# 2_MCU.net
KiCad netlist of a schematic drawn in Altium Designer
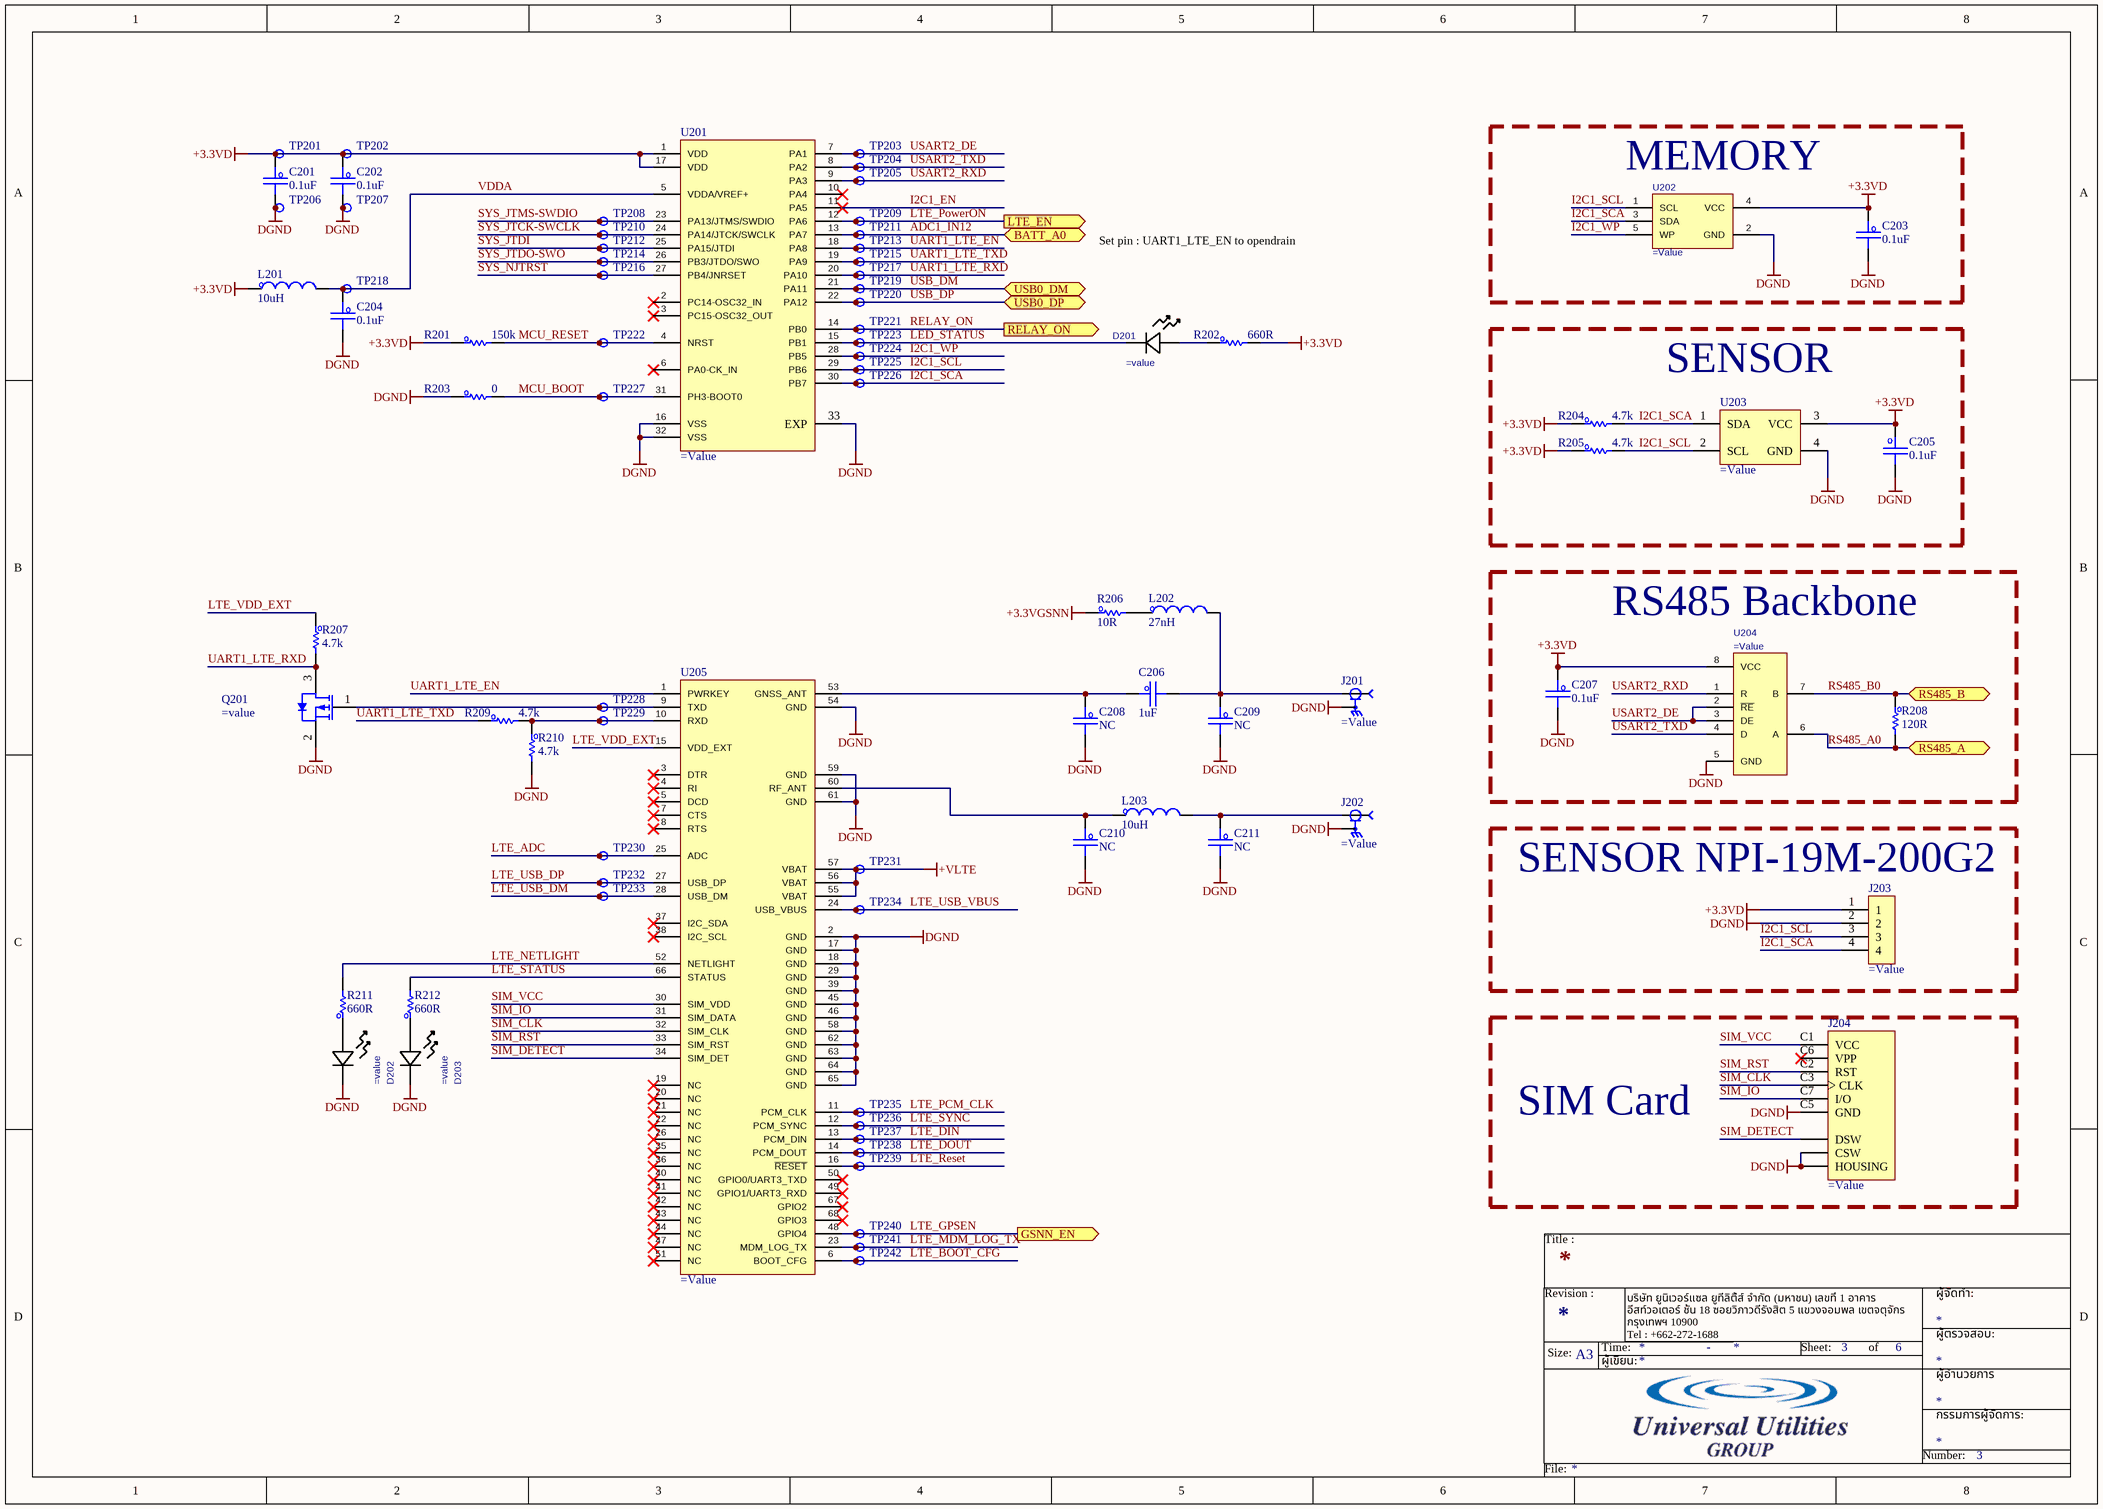
[diagram p0: 2_MCU.SchDoc]

(export (version "E")
  (design (tool "Eeschema 10.0.6"))
  (components
    (comp (ref "C201")
      (value "0.1uF")
      (footprint "C_0603")
      (description "CAP CER 0.1UF 50V X7R 0603")
      (fields (field (name "MANUFACTURER") "KEMET") (field (name "PARTNUMBER") "C0603C104K5RACTU"))
      (libsource (lib "UUSymbol") (part "C_Capacitor"))
    )
    (comp (ref "C202")
      (value "0.1uF")
      (footprint "C_0603")
      (description "CAP CER 0.1UF 50V X7R 0603")
      (fields (field (name "MANUFACTURER") "KEMET") (field (name "PARTNUMBER") "C0603C104K5RACTU"))
      (libsource (lib "UUSymbol") (part "C_Capacitor"))
    )
    (comp (ref "C203")
      (value "0.1uF")
      (footprint "C_0603")
      (description "CAP CER 0.1UF 50V X7R 0603")
      (fields (field (name "MANUFACTURER") "KEMET") (field (name "PARTNUMBER") "C0603C104K5RACTU"))
      (libsource (lib "UUSymbol") (part "C_Capacitor"))
    )
    (comp (ref "C204")
      (value "0.1uF")
      (footprint "C_0603")
      (description "CAP CER 0.1UF 50V X7R 0603")
      (fields (field (name "MANUFACTURER") "KEMET") (field (name "PARTNUMBER") "C0603C104K5RACTU"))
      (libsource (lib "UUSymbol") (part "C_Capacitor"))
    )
    (comp (ref "C205")
      (value "0.1uF")
      (footprint "C_0603")
      (description "CAP CER 0.1UF 50V X7R 0603")
      (fields (field (name "MANUFACTURER") "KEMET") (field (name "PARTNUMBER") "C0603C104K5RACTU"))
      (libsource (lib "UUSymbol") (part "C_Capacitor"))
    )
    (comp (ref "C206")
      (value "1uF")
      (footprint "C_0603")
      (description "Capacitor")
      (libsource (lib "UUSymbol") (part "C_Capacitor"))
    )
    (comp (ref "C207")
      (value "0.1uF")
      (footprint "C_0603")
      (description "CAP CER 0.1UF 50V X7R 0603")
      (fields (field (name "MANUFACTURER") "KEMET") (field (name "PARTNUMBER") "C0603C104K5RACTU"))
      (libsource (lib "UUSymbol") (part "C_Capacitor"))
    )
    (comp (ref "C208")
      (value "NC")
      (footprint "C_0603")
      (description "Capacitor")
      (libsource (lib "UUSymbol") (part "C_Capacitor"))
    )
    (comp (ref "C209")
      (value "NC")
      (footprint "C_0603")
      (description "Capacitor")
      (libsource (lib "UUSymbol") (part "C_Capacitor"))
    )
    (comp (ref "C210")
      (value "NC")
      (footprint "C_0603")
      (description "Capacitor")
      (libsource (lib "UUSymbol") (part "C_Capacitor"))
    )
    (comp (ref "C211")
      (value "NC")
      (footprint "C_0603")
      (description "Capacitor")
      (libsource (lib "UUSymbol") (part "C_Capacitor"))
    )
    (comp (ref "D201")
      (value "~")
      (footprint "LED_0VS75000_WRE")
      (description "LED BLUE CLEAR 0603 SMD")
      (fields (field (name "MANUFACTURER") "Wurth Electronics") (field (name "PARTNUMBER") "150060VS75000"))
      (libsource (lib "UUSymbol") (part "D_LED_150060BS75000"))
    )
    (comp (ref "D202")
      (value "~")
      (footprint "LED_0VS75000_WRE")
      (description "LED BLUE CLEAR 0603 SMD")
      (fields (field (name "MANUFACTURER") "Wurth Electronics") (field (name "PARTNUMBER") "150060VS75000"))
      (libsource (lib "UUSymbol") (part "D_LED_150060BS75000"))
    )
    (comp (ref "D203")
      (value "~")
      (footprint "LED_0VS75000_WRE")
      (description "LED BLUE CLEAR 0603 SMD")
      (fields (field (name "MANUFACTURER") "Wurth Electronics") (field (name "PARTNUMBER") "150060VS75000"))
      (libsource (lib "UUSymbol") (part "D_LED_150060BS75000"))
    )
    (comp (ref "J201")
      (value "~")
      (footprint "MOLEX_0734120114")
      (description "CONN UMC RCPT STR 50 OHM SMD")
      (fields (field (name "PARTNUMBER") "0734120114") (field (name "MANUFACTURER") "Molex"))
      (libsource (lib "UUSymbol") (part "CON_U.FL"))
    )
    (comp (ref "J202")
      (value "~")
      (footprint "MOLEX_0734120114")
      (description "CONN UMC RCPT STR 50 OHM SMD")
      (fields (field (name "PARTNUMBER") "0734120114") (field (name "MANUFACTURER") "Molex"))
      (libsource (lib "UUSymbol") (part "CON_U.FL"))
    )
    (comp (ref "J203")
      (value "~")
      (footprint "CON_4P_PADSENSOR")
      (description "Connector 4 position")
      (libsource (lib "UUSymbol") (part "CON_4P_Heder"))
    )
    (comp (ref "J204")
      (value "~")
      (footprint "JAE_SF72S006VBDR2500")
      (description "NANO SIM CARD CONNECTOR")
      (fields (field (name "PARTNUMBER") "SF72S006VBDR2500") (field (name "MANUFACTURER") "JAE Electronics"))
      (libsource (lib "UUSymbol") (part "CON_SIM_NanoSP"))
    )
    (comp (ref "L201")
      (value "10uH")
      (footprint "L_0603")
      (description "10µH Shielded Multilayer Inductor 250mA 1.05Ohm 0603 (1608 Metric)")
      (fields (field (name "MANUFACTURER") "TDK Corporation") (field (name "PARTNUMBER") "MLZ1608M100WT000"))
      (libsource (lib "UUSymbol") (part "L_Inductor"))
    )
    (comp (ref "L202")
      (value "27nH")
      (footprint "L_0603")
      (description "10µH Shielded Multilayer Inductor 250mA 1.05Ohm 0603 (1608 Metric)")
      (fields (field (name "MANUFACTURER") "TDK Corporation") (field (name "PARTNUMBER") "MLZ1608M100WT000"))
      (libsource (lib "UUSymbol") (part "L_Inductor"))
    )
    (comp (ref "L203")
      (value "10uH")
      (footprint "L_0603")
      (description "10µH Shielded Multilayer Inductor 250mA 1.05Ohm 0603 (1608 Metric)")
      (fields (field (name "MANUFACTURER") "TDK Corporation") (field (name "PARTNUMBER") "MLZ1608M100WT000"))
      (libsource (lib "UUSymbol") (part "L_Inductor"))
    )
    (comp (ref "Q201")
      (value "~")
      (footprint "SOT95P245X110-3M")
      (description "MOSFET P-CH 20V 600MA SOT23-3")
      (fields (field (name "MANUFACTURER") "Diodes Incorporated") (field (name "PARTNUMBER") "DMP2004K-7"))
      (libsource (lib "UUSymbol") (part "Q_PMOS_DMP2004K-7"))
    )
    (comp (ref "R201")
      (value "150k")
      (footprint "R_0603")
      (description "RES SMD 150K OHM 1% 1/10W 0603")
      (fields (field (name "MANUFACTURER") "Vishay Dale") (field (name "PARTNUMBER") "CRCW0603150KFKEAC"))
      (libsource (lib "UUSymbol") (part "R_Resister"))
    )
    (comp (ref "R202")
      (value "660R")
      (footprint "R_0603")
      (description "RES SMD 220 OHM 1% 1/10W 0603")
      (libsource (lib "UUSymbol") (part "R_Resister"))
    )
    (comp (ref "R203")
      (value "0")
      (footprint "R_0603")
      (description "RES SMD 0 OHM JUMP 1/10W 0603")
      (fields (field (name "MANUFACTURER") "Vishay Dale") (field (name "PARTNUMBER") "CRCW06030000Z0EBC"))
      (libsource (lib "UUSymbol") (part "R_Resister"))
    )
    (comp (ref "R204")
      (value "4.7k")
      (footprint "R_0603")
      (description "RES 4.7K OHM 5% 1/10W 0603")
      (fields (field (name "MANUFACTURER") "Vishay Dale") (field (name "PARTNUMBER") "CRCW06034K70JNEBC"))
      (libsource (lib "UUSymbol") (part "R_Resister"))
    )
    (comp (ref "R205")
      (value "4.7k")
      (footprint "R_0603")
      (description "RES 4.7K OHM 5% 1/10W 0603")
      (fields (field (name "MANUFACTURER") "Vishay Dale") (field (name "PARTNUMBER") "CRCW06034K70JNEBC"))
      (libsource (lib "UUSymbol") (part "R_Resister"))
    )
    (comp (ref "R206")
      (value "10R")
      (footprint "R_0603")
      (description "Resistor")
      (fields (field (name "MANUFACTURER") "Vishay") (field (name "PARTNUMBER") "EXB-2HV472JV"))
      (libsource (lib "UUSymbol") (part "R_Resister"))
    )
    (comp (ref "R207")
      (value "4.7k")
      (footprint "R_0603")
      (description "RES 4.7K OHM 5% 1/10W 0603")
      (fields (field (name "MANUFACTURER") "Vishay Dale") (field (name "PARTNUMBER") "CRCW06034K70JNEBC"))
      (libsource (lib "UUSymbol") (part "R_Resister"))
    )
    (comp (ref "R208")
      (value "120R")
      (footprint "R_0603")
      (description "RES SMD 120 OHM 1% 1/3W 0603")
      (fields (field (name "MANUFACTURER") "Vishay Dale") (field (name "PARTNUMBER") "CRCW0603120RFKEAHP"))
      (libsource (lib "UUSymbol") (part "R_Resister"))
    )
    (comp (ref "R209")
      (value "4.7k")
      (footprint "R_0603")
      (description "RES 4.7K OHM 5% 1/10W 0603")
      (fields (field (name "MANUFACTURER") "Vishay Dale") (field (name "PARTNUMBER") "CRCW06034K70JNEBC"))
      (libsource (lib "UUSymbol") (part "R_Resister"))
    )
    (comp (ref "R210")
      (value "4.7k")
      (footprint "R_0603")
      (description "RES 4.7K OHM 5% 1/10W 0603")
      (fields (field (name "MANUFACTURER") "Vishay Dale") (field (name "PARTNUMBER") "CRCW06034K70JNEBC"))
      (libsource (lib "UUSymbol") (part "R_Resister"))
    )
    (comp (ref "R211")
      (value "660R")
      (footprint "R_0603")
      (description "RES SMD 220 OHM 1% 1/10W 0603")
      (libsource (lib "UUSymbol") (part "R_Resister"))
    )
    (comp (ref "R212")
      (value "660R")
      (footprint "R_0603")
      (description "RES SMD 220 OHM 1% 1/10W 0603")
      (libsource (lib "UUSymbol") (part "R_Resister"))
    )
    (comp (ref "TP201")
      (value "~")
      (footprint "TP_Testpoint")
      (description "TestPoint")
      (libsource (lib "UUSymbol") (part "TP_TestPoint"))
    )
    (comp (ref "TP202")
      (value "~")
      (footprint "TP_Testpoint")
      (description "TestPoint")
      (libsource (lib "UUSymbol") (part "TP_TestPoint"))
    )
    (comp (ref "TP203")
      (value "~")
      (footprint "TP_Testpoint")
      (description "TestPoint")
      (libsource (lib "UUSymbol") (part "TP_TestPoint"))
    )
    (comp (ref "TP204")
      (value "~")
      (footprint "TP_Testpoint")
      (description "TestPoint")
      (libsource (lib "UUSymbol") (part "TP_TestPoint"))
    )
    (comp (ref "TP205")
      (value "~")
      (footprint "TP_Testpoint")
      (description "TestPoint")
      (libsource (lib "UUSymbol") (part "TP_TestPoint"))
    )
    (comp (ref "TP206")
      (value "~")
      (footprint "TP_Testpoint")
      (description "TestPoint")
      (libsource (lib "UUSymbol") (part "TP_TestPoint"))
    )
    (comp (ref "TP207")
      (value "~")
      (footprint "TP_Testpoint")
      (description "TestPoint")
      (libsource (lib "UUSymbol") (part "TP_TestPoint"))
    )
    (comp (ref "TP208")
      (value "~")
      (footprint "TP_Testpoint")
      (description "TestPoint")
      (libsource (lib "UUSymbol") (part "TP_TestPoint"))
    )
    (comp (ref "TP209")
      (value "~")
      (footprint "TP_Testpoint")
      (description "TestPoint")
      (libsource (lib "UUSymbol") (part "TP_TestPoint"))
    )
    (comp (ref "TP210")
      (value "~")
      (footprint "TP_Testpoint")
      (description "TestPoint")
      (libsource (lib "UUSymbol") (part "TP_TestPoint"))
    )
    (comp (ref "TP211")
      (value "~")
      (footprint "TP_Testpoint")
      (description "TestPoint")
      (libsource (lib "UUSymbol") (part "TP_TestPoint"))
    )
    (comp (ref "TP212")
      (value "~")
      (footprint "TP_Testpoint")
      (description "TestPoint")
      (libsource (lib "UUSymbol") (part "TP_TestPoint"))
    )
    (comp (ref "TP213")
      (value "~")
      (footprint "TP_Testpoint")
      (description "TestPoint")
      (libsource (lib "UUSymbol") (part "TP_TestPoint"))
    )
    (comp (ref "TP214")
      (value "~")
      (footprint "TP_Testpoint")
      (description "TestPoint")
      (libsource (lib "UUSymbol") (part "TP_TestPoint"))
    )
    (comp (ref "TP215")
      (value "~")
      (footprint "TP_Testpoint")
      (description "TestPoint")
      (libsource (lib "UUSymbol") (part "TP_TestPoint"))
    )
    (comp (ref "TP216")
      (value "~")
      (footprint "TP_Testpoint")
      (description "TestPoint")
      (libsource (lib "UUSymbol") (part "TP_TestPoint"))
    )
    (comp (ref "TP217")
      (value "~")
      (footprint "TP_Testpoint")
      (description "TestPoint")
      (libsource (lib "UUSymbol") (part "TP_TestPoint"))
    )
    (comp (ref "TP218")
      (value "~")
      (footprint "TP_Testpoint")
      (description "TestPoint")
      (libsource (lib "UUSymbol") (part "TP_TestPoint"))
    )
    (comp (ref "TP219")
      (value "~")
      (footprint "TP_Testpoint")
      (description "TestPoint")
      (libsource (lib "UUSymbol") (part "TP_TestPoint"))
    )
    (comp (ref "TP220")
      (value "~")
      (footprint "TP_Testpoint")
      (description "TestPoint")
      (libsource (lib "UUSymbol") (part "TP_TestPoint"))
    )
    (comp (ref "TP221")
      (value "~")
      (footprint "TP_Testpoint")
      (description "TestPoint")
      (libsource (lib "UUSymbol") (part "TP_TestPoint"))
    )
    (comp (ref "TP222")
      (value "~")
      (footprint "TP_Testpoint")
      (description "TestPoint")
      (libsource (lib "UUSymbol") (part "TP_TestPoint"))
    )
    (comp (ref "TP223")
      (value "~")
      (footprint "TP_Testpoint")
      (description "TestPoint")
      (libsource (lib "UUSymbol") (part "TP_TestPoint"))
    )
    (comp (ref "TP224")
      (value "~")
      (footprint "TP_Testpoint")
      (description "TestPoint")
      (libsource (lib "UUSymbol") (part "TP_TestPoint"))
    )
    (comp (ref "TP225")
      (value "~")
      (footprint "TP_Testpoint")
      (description "TestPoint")
      (libsource (lib "UUSymbol") (part "TP_TestPoint"))
    )
    (comp (ref "TP226")
      (value "~")
      (footprint "TP_Testpoint")
      (description "TestPoint")
      (libsource (lib "UUSymbol") (part "TP_TestPoint"))
    )
    (comp (ref "TP227")
      (value "~")
      (footprint "TP_Testpoint")
      (description "TestPoint")
      (libsource (lib "UUSymbol") (part "TP_TestPoint"))
    )
    (comp (ref "TP228")
      (value "~")
      (footprint "TP_Testpoint")
      (description "TestPoint")
      (libsource (lib "UUSymbol") (part "TP_TestPoint"))
    )
    (comp (ref "TP229")
      (value "~")
      (footprint "TP_Testpoint")
      (description "TestPoint")
      (libsource (lib "UUSymbol") (part "TP_TestPoint"))
    )
    (comp (ref "TP230")
      (value "~")
      (footprint "TP_Testpoint")
      (description "TestPoint")
      (libsource (lib "UUSymbol") (part "TP_TestPoint"))
    )
    (comp (ref "TP231")
      (value "~")
      (footprint "TP_Testpoint")
      (description "TestPoint")
      (libsource (lib "UUSymbol") (part "TP_TestPoint"))
    )
    (comp (ref "TP232")
      (value "~")
      (footprint "TP_Testpoint")
      (description "TestPoint")
      (libsource (lib "UUSymbol") (part "TP_TestPoint"))
    )
    (comp (ref "TP233")
      (value "~")
      (footprint "TP_Testpoint")
      (description "TestPoint")
      (libsource (lib "UUSymbol") (part "TP_TestPoint"))
    )
    (comp (ref "TP234")
      (value "~")
      (footprint "TP_Testpoint")
      (description "TestPoint")
      (libsource (lib "UUSymbol") (part "TP_TestPoint"))
    )
    (comp (ref "TP235")
      (value "~")
      (footprint "TP_Testpoint")
      (description "TestPoint")
      (libsource (lib "UUSymbol") (part "TP_TestPoint"))
    )
    (comp (ref "TP236")
      (value "~")
      (footprint "TP_Testpoint")
      (description "TestPoint")
      (libsource (lib "UUSymbol") (part "TP_TestPoint"))
    )
    (comp (ref "TP237")
      (value "~")
      (footprint "TP_Testpoint")
      (description "TestPoint")
      (libsource (lib "UUSymbol") (part "TP_TestPoint"))
    )
    (comp (ref "TP238")
      (value "~")
      (footprint "TP_Testpoint")
      (description "TestPoint")
      (libsource (lib "UUSymbol") (part "TP_TestPoint"))
    )
    (comp (ref "TP239")
      (value "~")
      (footprint "TP_Testpoint")
      (description "TestPoint")
      (libsource (lib "UUSymbol") (part "TP_TestPoint"))
    )
    (comp (ref "TP240")
      (value "~")
      (footprint "TP_Testpoint")
      (description "TestPoint")
      (libsource (lib "UUSymbol") (part "TP_TestPoint"))
    )
    (comp (ref "TP241")
      (value "~")
      (footprint "TP_Testpoint")
      (description "TestPoint")
      (libsource (lib "UUSymbol") (part "TP_TestPoint"))
    )
    (comp (ref "TP242")
      (value "~")
      (footprint "TP_Testpoint")
      (description "TestPoint")
      (libsource (lib "UUSymbol") (part "TP_TestPoint"))
    )
    (comp (ref "U201")
      (value "~")
      (footprint "QFN50P500X500X60-33N")
      (description "IC MCU 32BIT 256KB FLSH 32UFQFPN")
      (fields (field (name "PARTNUMBER") "STM32L432KCU6") (field (name "MANUFACTURER") "STMicroelectronics"))
      (libsource (lib "UUSymbol") (part "IC_MCU_STM32L432"))
    )
    (comp (ref "U202")
      (value "~")
      (footprint "SOT95P280X100-5N")
      (description "IC EEPROM 4KBIT I2C 1MHZ SOT23-5")
      (fields
        (field (name "MANUFACTURER") "Microchip Technology")
        (field (name "PARTNUMBER") "AT24C04D-STUM-T")
      )
      (libsource (lib "UUSymbol") (part "IC_MEM_AT24C04D-STUM-T"))
    )
    (comp (ref "U203")
      (value "~")
      (footprint "XDCR_SHT40-AD1B-R2")
      (description "SENSOR HUMIDITY 100 RH SMD")
      (fields (field (name "PARTNUMBER") "SHT40-AD1B-R3") (field (name "MANUFACTURER") "Sensirion AG"))
      (libsource (lib "UUSymbol") (part "IC_SEN_SHT40-AD1B-R3"))
    )
    (comp (ref "U204")
      (value "~")
      (footprint "D0008A_L")
      (description "IC TRANSCEIVER HALF 1/1 8SOIC")
      (fields (field (name "MANUFACTURER") "Texas Instruments") (field (name "PARTNUMBER") "SN65HVD11DR"))
      (libsource (lib "UUSymbol") (part "IC_TRAN_THVD1505DR"))
    )
    (comp (ref "U205")
      (value "~")
      (footprint "SIM7000A S2-1000")
      (description "DGTL ISO 5000VRMS 6CH 16SOIC")
      (fields
        (field (name "MANUFACTURER") "SIMCom Wireless Solutions Limited")
        (field (name "PARTNUMBER") "SIM7000G")
      )
      (libsource (lib "UUSymbol") (part "IC_MOD_SIM7000X"))
    )
  )
  (nets
    (net (code "1") (name "+3.3VD") (class "Default")
      (node (ref "C201") (pin "1") (pinfunction "1_1") (pintype "passive"))
      (node (ref "C202") (pin "1") (pinfunction "1_1") (pintype "passive"))
      (node (ref "C203") (pin "1") (pinfunction "1_1") (pintype "passive"))
      (node (ref "C205") (pin "1") (pinfunction "1_1") (pintype "passive"))
      (node (ref "C207") (pin "1") (pinfunction "1_1") (pintype "passive"))
      (node (ref "J203") (pin "1") (pinfunction "1_1") (pintype "passive"))
      (node (ref "L201") (pin "1") (pinfunction "1_1") (pintype "passive"))
      (node (ref "R201") (pin "1") (pinfunction "1_1") (pintype "passive"))
      (node (ref "R202") (pin "2") (pinfunction "2_2") (pintype "passive"))
      (node (ref "R204") (pin "1") (pinfunction "1_1") (pintype "passive"))
      (node (ref "R205") (pin "1") (pinfunction "1_1") (pintype "passive"))
      (node (ref "TP201") (pin "1") (pinfunction "1_1") (pintype "passive"))
      (node (ref "TP202") (pin "1") (pinfunction "1_1") (pintype "passive"))
      (node (ref "U201") (pin "1") (pinfunction "VDD_1") (pintype "passive"))
      (node (ref "U201") (pin "17") (pinfunction "VDD_17") (pintype "passive"))
      (node (ref "U202") (pin "4") (pinfunction "VCC_4") (pintype "passive"))
      (node (ref "U203") (pin "3") (pinfunction "VCC_3") (pintype "passive"))
      (node (ref "U204") (pin "8") (pinfunction "VCC_8") (pintype "passive"))
    )
    (net (code "2") (name "+3.3VGSNN") (class "Default")
      (node (ref "R206") (pin "1") (pinfunction "1_1") (pintype "passive"))
    )
    (net (code "3") (name "+VLTE") (class "Default")
      (node (ref "TP231") (pin "1") (pinfunction "1_1") (pintype "passive"))
      (node (ref "U205") (pin "55") (pinfunction "VBAT_55") (pintype "passive"))
      (node (ref "U205") (pin "56") (pinfunction "VBAT_56") (pintype "passive"))
      (node (ref "U205") (pin "57") (pinfunction "VBAT_57") (pintype "passive"))
    )
    (net (code "4") (name "/ADC1_IN12") (class "Default")
      (node (ref "TP211") (pin "1") (pinfunction "1_1") (pintype "passive"))
      (node (ref "U201") (pin "13") (pinfunction "PA7_13") (pintype "passive"))
    )
    (net (code "5") (name "/I2C1_EN") (class "Default")
      (node (ref "U201") (pin "11") (pinfunction "PA5_11") (pintype "passive+no_connect"))
    )
    (net (code "6") (name "/I2C1_SCA") (class "Default")
      (node (ref "J203") (pin "4") (pinfunction "4_4") (pintype "passive"))
      (node (ref "R204") (pin "2") (pinfunction "2_2") (pintype "passive"))
      (node (ref "TP226") (pin "1") (pinfunction "1_1") (pintype "passive"))
      (node (ref "U201") (pin "30") (pinfunction "PB7_30") (pintype "passive"))
      (node (ref "U202") (pin "3") (pinfunction "SDA_3") (pintype "passive"))
      (node (ref "U203") (pin "1") (pinfunction "SDA_1") (pintype "passive"))
    )
    (net (code "7") (name "/I2C1_SCL") (class "Default")
      (node (ref "J203") (pin "3") (pinfunction "3_3") (pintype "passive"))
      (node (ref "R205") (pin "2") (pinfunction "2_2") (pintype "passive"))
      (node (ref "TP225") (pin "1") (pinfunction "1_1") (pintype "passive"))
      (node (ref "U201") (pin "29") (pinfunction "PB6_29") (pintype "passive"))
      (node (ref "U202") (pin "1") (pinfunction "SCL_1") (pintype "passive"))
      (node (ref "U203") (pin "2") (pinfunction "SCL_2") (pintype "passive"))
    )
    (net (code "8") (name "/I2C1_WP") (class "Default")
      (node (ref "TP224") (pin "1") (pinfunction "1_1") (pintype "passive"))
      (node (ref "U201") (pin "28") (pinfunction "PB5_28") (pintype "passive"))
      (node (ref "U202") (pin "5") (pinfunction "WP_5") (pintype "passive"))
    )
    (net (code "9") (name "/LED_STATUS") (class "Default")
      (node (ref "D201") (pin "2") (pinfunction "2_2") (pintype "passive"))
      (node (ref "TP223") (pin "1") (pinfunction "1_1") (pintype "passive"))
      (node (ref "U201") (pin "15") (pinfunction "PB1_15") (pintype "passive"))
    )
    (net (code "10") (name "/LTE_ADC") (class "Default")
      (node (ref "TP230") (pin "1") (pinfunction "1_1") (pintype "passive"))
      (node (ref "U205") (pin "25") (pinfunction "ADC_25") (pintype "passive"))
    )
    (net (code "11") (name "/LTE_BOOT_CFG") (class "Default")
      (node (ref "TP242") (pin "1") (pinfunction "1_1") (pintype "passive"))
      (node (ref "U205") (pin "6") (pinfunction "BOOT_CFG_6") (pintype "passive"))
    )
    (net (code "12") (name "/LTE_DIN") (class "Default")
      (node (ref "TP237") (pin "1") (pinfunction "1_1") (pintype "passive"))
      (node (ref "U205") (pin "13") (pinfunction "PCM_DIN_13") (pintype "passive"))
    )
    (net (code "13") (name "/LTE_DOUT") (class "Default")
      (node (ref "TP238") (pin "1") (pinfunction "1_1") (pintype "passive"))
      (node (ref "U205") (pin "14") (pinfunction "PCM_DOUT_14") (pintype "passive"))
    )
    (net (code "14") (name "/LTE_GPSEN") (class "Default")
      (node (ref "TP240") (pin "1") (pinfunction "1_1") (pintype "passive"))
      (node (ref "U205") (pin "48") (pinfunction "GPIO4_48") (pintype "passive"))
    )
    (net (code "15") (name "/LTE_MDM_LOG_TX") (class "Default")
      (node (ref "TP241") (pin "1") (pinfunction "1_1") (pintype "passive"))
      (node (ref "U205") (pin "23") (pinfunction "MDM_LOG_TX_23") (pintype "passive"))
    )
    (net (code "16") (name "/LTE_NETLIGHT") (class "Default")
      (node (ref "R211") (pin "2") (pinfunction "2_2") (pintype "passive"))
      (node (ref "U205") (pin "52") (pinfunction "NETLIGHT_52") (pintype "passive"))
    )
    (net (code "17") (name "/LTE_PCM_CLK") (class "Default")
      (node (ref "TP235") (pin "1") (pinfunction "1_1") (pintype "passive"))
      (node (ref "U205") (pin "11") (pinfunction "PCM_CLK_11") (pintype "passive"))
    )
    (net (code "18") (name "/LTE_PowerON") (class "Default")
      (node (ref "TP209") (pin "1") (pinfunction "1_1") (pintype "passive"))
      (node (ref "U201") (pin "12") (pinfunction "PA6_12") (pintype "passive"))
    )
    (net (code "19") (name "/LTE_Reset") (class "Default")
      (node (ref "TP239") (pin "1") (pinfunction "1_1") (pintype "passive"))
      (node (ref "U205") (pin "16") (pinfunction "~{RESET}_16") (pintype "passive"))
    )
    (net (code "20") (name "/LTE_STATUS") (class "Default")
      (node (ref "R212") (pin "2") (pinfunction "2_2") (pintype "passive"))
      (node (ref "U205") (pin "66") (pinfunction "STATUS_66") (pintype "passive"))
    )
    (net (code "21") (name "/LTE_SYNC") (class "Default")
      (node (ref "TP236") (pin "1") (pinfunction "1_1") (pintype "passive"))
      (node (ref "U205") (pin "12") (pinfunction "PCM_SYNC_12") (pintype "passive"))
    )
    (net (code "22") (name "/LTE_USB_DM") (class "Default")
      (node (ref "TP233") (pin "1") (pinfunction "1_1") (pintype "passive"))
      (node (ref "U205") (pin "28") (pinfunction "USB_DM_28") (pintype "passive"))
    )
    (net (code "23") (name "/LTE_USB_DP") (class "Default")
      (node (ref "TP232") (pin "1") (pinfunction "1_1") (pintype "passive"))
      (node (ref "U205") (pin "27") (pinfunction "USB_DP_27") (pintype "passive"))
    )
    (net (code "24") (name "/LTE_USB_VBUS") (class "Default")
      (node (ref "TP234") (pin "1") (pinfunction "1_1") (pintype "passive"))
      (node (ref "U205") (pin "24") (pinfunction "USB_VBUS_24") (pintype "passive"))
    )
    (net (code "25") (name "/LTE_VDD_EXT") (class "Default")
      (node (ref "R207") (pin "1") (pinfunction "1_1") (pintype "passive"))
      (node (ref "U205") (pin "15") (pinfunction "VDD_EXT_15") (pintype "passive"))
    )
    (net (code "26") (name "/MCU_BOOT") (class "Default")
      (node (ref "R203") (pin "2") (pinfunction "2_2") (pintype "passive"))
      (node (ref "TP227") (pin "1") (pinfunction "1_1") (pintype "passive"))
      (node (ref "U201") (pin "31") (pinfunction "PH3-BOOT0_31") (pintype "passive"))
    )
    (net (code "27") (name "/MCU_RESET") (class "Default")
      (node (ref "R201") (pin "2") (pinfunction "2_2") (pintype "passive"))
      (node (ref "TP222") (pin "1") (pinfunction "1_1") (pintype "passive"))
      (node (ref "U201") (pin "4") (pinfunction "NRST_4") (pintype "passive"))
    )
    (net (code "28") (name "/RELAY_ON") (class "Default")
      (node (ref "TP221") (pin "1") (pinfunction "1_1") (pintype "passive"))
      (node (ref "U201") (pin "14") (pinfunction "PB0_14") (pintype "passive"))
    )
    (net (code "29") (name "/RS485_A0") (class "Default")
      (node (ref "R208") (pin "2") (pinfunction "2_2") (pintype "passive"))
      (node (ref "U204") (pin "6") (pinfunction "A_6") (pintype "passive"))
    )
    (net (code "30") (name "/RS485_B0") (class "Default")
      (node (ref "R208") (pin "1") (pinfunction "1_1") (pintype "passive"))
      (node (ref "U204") (pin "7") (pinfunction "B_7") (pintype "passive"))
    )
    (net (code "31") (name "/SIM_CLK") (class "Default")
      (node (ref "J204") (pin "C3") (pinfunction "CLK_C3") (pintype "passive"))
      (node (ref "U205") (pin "32") (pinfunction "SIM_CLK_32") (pintype "passive"))
    )
    (net (code "32") (name "/SIM_DETECT") (class "Default")
      (node (ref "J204") (pin "DSW") (pinfunction "DSW_DSW") (pintype "passive"))
      (node (ref "U205") (pin "34") (pinfunction "SIM_DET_34") (pintype "passive"))
    )
    (net (code "33") (name "/SIM_IO") (class "Default")
      (node (ref "J204") (pin "C7") (pinfunction "I/O_C7") (pintype "passive"))
      (node (ref "U205") (pin "31") (pinfunction "SIM_DATA_31") (pintype "passive"))
    )
    (net (code "34") (name "/SIM_RST") (class "Default")
      (node (ref "J204") (pin "C2") (pinfunction "RST_C2") (pintype "passive"))
      (node (ref "U205") (pin "33") (pinfunction "SIM_RST_33") (pintype "passive"))
    )
    (net (code "35") (name "/SIM_VCC") (class "Default")
      (node (ref "J204") (pin "C1") (pinfunction "VCC_C1") (pintype "passive"))
      (node (ref "U205") (pin "30") (pinfunction "SIM_VDD_30") (pintype "passive"))
    )
    (net (code "36") (name "/SYS_JTCK-SWCLK") (class "Default")
      (node (ref "TP210") (pin "1") (pinfunction "1_1") (pintype "passive"))
      (node (ref "U201") (pin "24") (pinfunction "PA14/JTCK/SWCLK_24") (pintype "passive"))
    )
    (net (code "37") (name "/SYS_JTDI") (class "Default")
      (node (ref "TP212") (pin "1") (pinfunction "1_1") (pintype "passive"))
      (node (ref "U201") (pin "25") (pinfunction "PA15/JTDI_25") (pintype "passive"))
    )
    (net (code "38") (name "/SYS_JTDO-SWO") (class "Default")
      (node (ref "TP214") (pin "1") (pinfunction "1_1") (pintype "passive"))
      (node (ref "U201") (pin "26") (pinfunction "PB3/JTDO/SWO_26") (pintype "passive"))
    )
    (net (code "39") (name "/SYS_JTMS-SWDIO") (class "Default")
      (node (ref "TP208") (pin "1") (pinfunction "1_1") (pintype "passive"))
      (node (ref "U201") (pin "23") (pinfunction "PA13/JTMS/SWDIO_23") (pintype "passive"))
    )
    (net (code "40") (name "/SYS_NJTRST") (class "Default")
      (node (ref "TP216") (pin "1") (pinfunction "1_1") (pintype "passive"))
      (node (ref "U201") (pin "27") (pinfunction "PB4/JNRSET_27") (pintype "passive"))
    )
    (net (code "41") (name "/UART1_LTE_EN") (class "Default")
      (node (ref "TP213") (pin "1") (pinfunction "1_1") (pintype "passive"))
      (node (ref "U201") (pin "18") (pinfunction "PA8_18") (pintype "passive"))
      (node (ref "U205") (pin "1") (pinfunction "PWRKEY_1") (pintype "passive"))
    )
    (net (code "42") (name "/UART1_LTE_RXD") (class "Default")
      (node (ref "Q201") (pin "3") (pinfunction "D_3") (pintype "passive"))
      (node (ref "R207") (pin "2") (pinfunction "2_2") (pintype "passive"))
      (node (ref "TP217") (pin "1") (pinfunction "1_1") (pintype "passive"))
      (node (ref "U201") (pin "20") (pinfunction "PA10_20") (pintype "passive"))
    )
    (net (code "43") (name "/UART1_LTE_TXD") (class "Default")
      (node (ref "R209") (pin "1") (pinfunction "1_1") (pintype "passive"))
      (node (ref "TP215") (pin "1") (pinfunction "1_1") (pintype "passive"))
      (node (ref "U201") (pin "19") (pinfunction "PA9_19") (pintype "passive"))
    )
    (net (code "44") (name "/USART2_DE") (class "Default")
      (node (ref "TP203") (pin "1") (pinfunction "1_1") (pintype "passive"))
      (node (ref "U201") (pin "7") (pinfunction "PA1_7") (pintype "passive"))
      (node (ref "U204") (pin "2") (pinfunction "~{RE}_2") (pintype "passive"))
      (node (ref "U204") (pin "3") (pinfunction "DE_3") (pintype "passive"))
    )
    (net (code "45") (name "/USART2_RXD") (class "Default")
      (node (ref "TP205") (pin "1") (pinfunction "1_1") (pintype "passive"))
      (node (ref "U201") (pin "9") (pinfunction "PA3_9") (pintype "passive"))
      (node (ref "U204") (pin "1") (pinfunction "R_1") (pintype "passive"))
    )
    (net (code "46") (name "/USART2_TXD") (class "Default")
      (node (ref "TP204") (pin "1") (pinfunction "1_1") (pintype "passive"))
      (node (ref "U201") (pin "8") (pinfunction "PA2_8") (pintype "passive"))
      (node (ref "U204") (pin "4") (pinfunction "D_4") (pintype "passive"))
    )
    (net (code "47") (name "/USB_DM") (class "Default")
      (node (ref "TP219") (pin "1") (pinfunction "1_1") (pintype "passive"))
      (node (ref "U201") (pin "21") (pinfunction "PA11_21") (pintype "passive"))
    )
    (net (code "48") (name "/USB_DP") (class "Default")
      (node (ref "TP220") (pin "1") (pinfunction "1_1") (pintype "passive"))
      (node (ref "U201") (pin "22") (pinfunction "PA12_22") (pintype "passive"))
    )
    (net (code "49") (name "/VDDA") (class "Default")
      (node (ref "C204") (pin "1") (pinfunction "1_1") (pintype "passive"))
      (node (ref "L201") (pin "2") (pinfunction "2_2") (pintype "passive"))
      (node (ref "TP218") (pin "1") (pinfunction "1_1") (pintype "passive"))
      (node (ref "U201") (pin "5") (pinfunction "VDDA/VREF+_5") (pintype "passive"))
    )
    (net (code "50") (name "DGND") (class "Default")
      (node (ref "C201") (pin "2") (pinfunction "2_2") (pintype "passive"))
      (node (ref "C202") (pin "2") (pinfunction "2_2") (pintype "passive"))
      (node (ref "C203") (pin "2") (pinfunction "2_2") (pintype "passive"))
      (node (ref "C204") (pin "2") (pinfunction "2_2") (pintype "passive"))
      (node (ref "C205") (pin "2") (pinfunction "2_2") (pintype "passive"))
      (node (ref "C207") (pin "2") (pinfunction "2_2") (pintype "passive"))
      (node (ref "C208") (pin "2") (pinfunction "2_2") (pintype "passive"))
      (node (ref "C209") (pin "2") (pinfunction "2_2") (pintype "passive"))
      (node (ref "C210") (pin "2") (pinfunction "2_2") (pintype "passive"))
      (node (ref "C211") (pin "2") (pinfunction "2_2") (pintype "passive"))
      (node (ref "D202") (pin "2") (pinfunction "2_2") (pintype "passive"))
      (node (ref "D203") (pin "2") (pinfunction "2_2") (pintype "passive"))
      (node (ref "J201") (pin "2") (pinfunction "2_2") (pintype "passive"))
      (node (ref "J202") (pin "2") (pinfunction "2_2") (pintype "passive"))
      (node (ref "J203") (pin "2") (pinfunction "2_2") (pintype "passive"))
      (node (ref "J204") (pin "C5") (pinfunction "GND_C5") (pintype "passive"))
      (node (ref "J204") (pin "CSW") (pinfunction "CSW_CSW") (pintype "passive"))
      (node (ref "J204") (pin "SH") (pinfunction "HOUSING_SH") (pintype "passive"))
      (node (ref "Q201") (pin "2") (pinfunction "S_2") (pintype "passive"))
      (node (ref "R203") (pin "1") (pinfunction "1_1") (pintype "passive"))
      (node (ref "R210") (pin "2") (pinfunction "2_2") (pintype "passive"))
      (node (ref "TP206") (pin "1") (pinfunction "1_1") (pintype "passive"))
      (node (ref "TP207") (pin "1") (pinfunction "1_1") (pintype "passive"))
      (node (ref "U201") (pin "16") (pinfunction "VSS_16") (pintype "passive"))
      (node (ref "U201") (pin "32") (pinfunction "VSS_32") (pintype "passive"))
      (node (ref "U201") (pin "33") (pinfunction "EXP_33") (pintype "passive"))
      (node (ref "U202") (pin "2") (pinfunction "GND_2") (pintype "passive"))
      (node (ref "U203") (pin "4") (pinfunction "GND_4") (pintype "passive"))
      (node (ref "U204") (pin "5") (pinfunction "GND_5") (pintype "passive"))
      (node (ref "U205") (pin "17") (pinfunction "GND_17") (pintype "passive"))
      (node (ref "U205") (pin "18") (pinfunction "GND_18") (pintype "passive"))
      (node (ref "U205") (pin "2") (pinfunction "GND_2") (pintype "passive"))
      (node (ref "U205") (pin "29") (pinfunction "GND_29") (pintype "passive"))
      (node (ref "U205") (pin "39") (pinfunction "GND_39") (pintype "passive"))
      (node (ref "U205") (pin "45") (pinfunction "GND_45") (pintype "passive"))
      (node (ref "U205") (pin "46") (pinfunction "GND_46") (pintype "passive"))
      (node (ref "U205") (pin "54") (pinfunction "GND_54") (pintype "passive"))
      (node (ref "U205") (pin "58") (pinfunction "GND_58") (pintype "passive"))
      (node (ref "U205") (pin "59") (pinfunction "GND_59") (pintype "passive"))
      (node (ref "U205") (pin "61") (pinfunction "GND_61") (pintype "passive"))
      (node (ref "U205") (pin "62") (pinfunction "GND_62") (pintype "passive"))
      (node (ref "U205") (pin "63") (pinfunction "GND_63") (pintype "passive"))
      (node (ref "U205") (pin "64") (pinfunction "GND_64") (pintype "passive"))
      (node (ref "U205") (pin "65") (pinfunction "GND_65") (pintype "passive"))
    )
    (net (code "51") (name "Net-(C206-Pad2)") (class "Default")
      (node (ref "C206") (pin "2") (pinfunction "2_2") (pintype "passive"))
      (node (ref "C209") (pin "1") (pinfunction "1_1") (pintype "passive"))
      (node (ref "J201") (pin "1") (pinfunction "1_1") (pintype "passive"))
      (node (ref "L202") (pin "2") (pinfunction "2_2") (pintype "passive"))
    )
    (net (code "52") (name "Net-(C211-Pad1)") (class "Default")
      (node (ref "C211") (pin "1") (pinfunction "1_1") (pintype "passive"))
      (node (ref "J202") (pin "1") (pinfunction "1_1") (pintype "passive"))
      (node (ref "L203") (pin "2") (pinfunction "2_2") (pintype "passive"))
    )
    (net (code "53") (name "Net-(D201-Pad1)") (class "Default")
      (node (ref "D201") (pin "1") (pinfunction "1_1") (pintype "passive"))
      (node (ref "R202") (pin "1") (pinfunction "1_1") (pintype "passive"))
    )
    (net (code "54") (name "Net-(D202-Pad1)") (class "Default")
      (node (ref "D202") (pin "1") (pinfunction "1_1") (pintype "passive"))
      (node (ref "R211") (pin "1") (pinfunction "1_1") (pintype "passive"))
    )
    (net (code "55") (name "Net-(D203-Pad1)") (class "Default")
      (node (ref "D203") (pin "1") (pinfunction "1_1") (pintype "passive"))
      (node (ref "R212") (pin "1") (pinfunction "1_1") (pintype "passive"))
    )
    (net (code "56") (name "Net-(L202-Pad1)") (class "Default")
      (node (ref "L202") (pin "1") (pinfunction "1_1") (pintype "passive"))
      (node (ref "R206") (pin "2") (pinfunction "2_2") (pintype "passive"))
    )
    (net (code "57") (name "Net-(Q201-G)") (class "Default")
      (node (ref "Q201") (pin "1") (pinfunction "G_1") (pintype "passive"))
      (node (ref "TP228") (pin "1") (pinfunction "1_1") (pintype "passive"))
      (node (ref "U205") (pin "9") (pinfunction "TXD_9") (pintype "passive"))
    )
    (net (code "58") (name "Net-(U205-GNSS_ANT)") (class "Default")
      (node (ref "C206") (pin "1") (pinfunction "1_1") (pintype "passive"))
      (node (ref "C208") (pin "1") (pinfunction "1_1") (pintype "passive"))
      (node (ref "U205") (pin "53") (pinfunction "GNSS_ANT_53") (pintype "passive"))
    )
    (net (code "59") (name "Net-(U205-RF_ANT)") (class "Default")
      (node (ref "C210") (pin "1") (pinfunction "1_1") (pintype "passive"))
      (node (ref "L203") (pin "1") (pinfunction "1_1") (pintype "passive"))
      (node (ref "U205") (pin "60") (pinfunction "RF_ANT_60") (pintype "passive"))
    )
    (net (code "60") (name "Net-(U205-RXD)") (class "Default")
      (node (ref "R209") (pin "2") (pinfunction "2_2") (pintype "passive"))
      (node (ref "R210") (pin "1") (pinfunction "1_1") (pintype "passive"))
      (node (ref "TP229") (pin "1") (pinfunction "1_1") (pintype "passive"))
      (node (ref "U205") (pin "10") (pinfunction "RXD_10") (pintype "passive"))
    )
    (net (code "61") (name "unconnected-(J204-VPP-PadC6)") (class "Default")
      (node (ref "J204") (pin "C6") (pinfunction "VPP_C6") (pintype "passive+no_connect"))
    )
    (net (code "62") (name "unconnected-(U201-PA0-CK_IN-Pad6)") (class "Default")
      (node (ref "U201") (pin "6") (pinfunction "PA0-CK_IN_6") (pintype "passive+no_connect"))
    )
    (net (code "63") (name "unconnected-(U201-PA4-Pad10)") (class "Default")
      (node (ref "U201") (pin "10") (pinfunction "PA4_10") (pintype "passive+no_connect"))
    )
    (net (code "64") (name "unconnected-(U201-PC14-OSC32_IN-Pad2)") (class "Default")
      (node (ref "U201") (pin "2") (pinfunction "PC14-OSC32_IN_2") (pintype "passive+no_connect"))
    )
    (net (code "65") (name "unconnected-(U201-PC15-OSC32_OUT-Pad3)") (class "Default")
      (node (ref "U201") (pin "3") (pinfunction "PC15-OSC32_OUT_3") (pintype "passive+no_connect"))
    )
    (net (code "66") (name "unconnected-(U205-CTS-Pad7)") (class "Default")
      (node (ref "U205") (pin "7") (pinfunction "CTS_7") (pintype "passive+no_connect"))
    )
    (net (code "67") (name "unconnected-(U205-DCD-Pad5)") (class "Default")
      (node (ref "U205") (pin "5") (pinfunction "DCD_5") (pintype "passive+no_connect"))
    )
    (net (code "68") (name "unconnected-(U205-DTR-Pad3)") (class "Default")
      (node (ref "U205") (pin "3") (pinfunction "DTR_3") (pintype "passive+no_connect"))
    )
    (net (code "69") (name "unconnected-(U205-GPIO0{slash}UART3_TXD-Pad50)") (class "Default")
      (node (ref "U205") (pin "50") (pinfunction "GPIO0/UART3_TXD_50") (pintype "passive+no_connect"))
    )
    (net (code "70") (name "unconnected-(U205-GPIO1{slash}UART3_RXD-Pad49)") (class "Default")
      (node (ref "U205") (pin "49") (pinfunction "GPIO1/UART3_RXD_49") (pintype "passive+no_connect"))
    )
    (net (code "71") (name "unconnected-(U205-GPIO2-Pad67)") (class "Default")
      (node (ref "U205") (pin "67") (pinfunction "GPIO2_67") (pintype "passive+no_connect"))
    )
    (net (code "72") (name "unconnected-(U205-GPIO3-Pad68)") (class "Default")
      (node (ref "U205") (pin "68") (pinfunction "GPIO3_68") (pintype "passive+no_connect"))
    )
    (net (code "73") (name "unconnected-(U205-I2C_SCL-Pad38)") (class "Default")
      (node (ref "U205") (pin "38") (pinfunction "I2C_SCL_38") (pintype "passive+no_connect"))
    )
    (net (code "74") (name "unconnected-(U205-I2C_SDA-Pad37)") (class "Default")
      (node (ref "U205") (pin "37") (pinfunction "I2C_SDA_37") (pintype "passive+no_connect"))
    )
    (net (code "75") (name "unconnected-(U205-NC-Pad19)") (class "Default")
      (node (ref "U205") (pin "19") (pinfunction "NC_19") (pintype "passive+no_connect"))
    )
    (net (code "76") (name "unconnected-(U205-NC-Pad20)") (class "Default")
      (node (ref "U205") (pin "20") (pinfunction "NC_20") (pintype "passive+no_connect"))
    )
    (net (code "77") (name "unconnected-(U205-NC-Pad21)") (class "Default")
      (node (ref "U205") (pin "21") (pinfunction "NC_21") (pintype "passive+no_connect"))
    )
    (net (code "78") (name "unconnected-(U205-NC-Pad22)") (class "Default")
      (node (ref "U205") (pin "22") (pinfunction "NC_22") (pintype "passive+no_connect"))
    )
    (net (code "79") (name "unconnected-(U205-NC-Pad26)") (class "Default")
      (node (ref "U205") (pin "26") (pinfunction "NC_26") (pintype "passive+no_connect"))
    )
    (net (code "80") (name "unconnected-(U205-NC-Pad35)") (class "Default")
      (node (ref "U205") (pin "35") (pinfunction "NC_35") (pintype "passive+no_connect"))
    )
    (net (code "81") (name "unconnected-(U205-NC-Pad36)") (class "Default")
      (node (ref "U205") (pin "36") (pinfunction "NC_36") (pintype "passive+no_connect"))
    )
    (net (code "82") (name "unconnected-(U205-NC-Pad40)") (class "Default")
      (node (ref "U205") (pin "40") (pinfunction "NC_40") (pintype "passive+no_connect"))
    )
    (net (code "83") (name "unconnected-(U205-NC-Pad41)") (class "Default")
      (node (ref "U205") (pin "41") (pinfunction "NC_41") (pintype "passive+no_connect"))
    )
    (net (code "84") (name "unconnected-(U205-NC-Pad42)") (class "Default")
      (node (ref "U205") (pin "42") (pinfunction "NC_42") (pintype "passive+no_connect"))
    )
    (net (code "85") (name "unconnected-(U205-NC-Pad43)") (class "Default")
      (node (ref "U205") (pin "43") (pinfunction "NC_43") (pintype "passive+no_connect"))
    )
    (net (code "86") (name "unconnected-(U205-NC-Pad44)") (class "Default")
      (node (ref "U205") (pin "44") (pinfunction "NC_44") (pintype "passive+no_connect"))
    )
    (net (code "87") (name "unconnected-(U205-NC-Pad47)") (class "Default")
      (node (ref "U205") (pin "47") (pinfunction "NC_47") (pintype "passive+no_connect"))
    )
    (net (code "88") (name "unconnected-(U205-NC-Pad51)") (class "Default")
      (node (ref "U205") (pin "51") (pinfunction "NC_51") (pintype "passive+no_connect"))
    )
    (net (code "89") (name "unconnected-(U205-RI-Pad4)") (class "Default")
      (node (ref "U205") (pin "4") (pinfunction "RI_4") (pintype "passive+no_connect"))
    )
    (net (code "90") (name "unconnected-(U205-RTS-Pad8)") (class "Default")
      (node (ref "U205") (pin "8") (pinfunction "RTS_8") (pintype "passive+no_connect"))
    )
  )
)
